# temperature_sensor.net
KiCad netlist of a schematic drawn in EAGLE
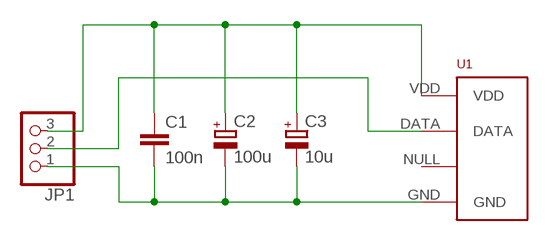
[diagram p0: schematic, sheet 1]

(export (version "E")
  (design (tool "Eeschema 10.0.6"))
  (components
    (comp (ref "C1")
      (value "100n")
      (footprint "eagle-import:C050-024X044")
      (libsource (lib "eagle-import") (part "C-EU050-024X044"))
    )
    (comp (ref "C2")
      (value "100u")
      (footprint "eagle-import:E2-5")
      (libsource (lib "eagle-import") (part "CPOL-EUE2-5"))
    )
    (comp (ref "C3")
      (value "10u")
      (footprint "eagle-import:E1,8-4")
      (libsource (lib "eagle-import") (part "CPOL-EUE1.8-4"))
    )
    (comp (ref "JP1")
      (value "PINHD-1X3")
      (footprint "eagle-import:1X03")
      (libsource (lib "eagle-import") (part "PINHD-1X3"))
    )
    (comp (ref "U1")
      (value "RHT03_DHT-22_AM2302RA")
      (footprint "eagle-import:RHT03_DHT-22_RA")
      (libsource (lib "eagle-import") (part "RHT03_DHT-22_AM2302RA"))
    )
  )
  (nets
    (net (code "1") (name "Net-(C1-Pad1)") (class "Default")
      (node (ref "C1") (pin "1") (pinfunction "1_1") (pintype "passive"))
      (node (ref "C2") (pin "+") (pinfunction "+_+") (pintype "passive"))
      (node (ref "C3") (pin "+") (pinfunction "+_+") (pintype "passive"))
      (node (ref "JP1") (pin "3") (pinfunction "3_3") (pintype "passive"))
      (node (ref "U1") (pin "VDD") (pinfunction "VDD_VDD") (pintype "power_in"))
    )
    (net (code "2") (name "Net-(C1-Pad2)") (class "Default")
      (node (ref "C1") (pin "2") (pinfunction "2_2") (pintype "passive"))
      (node (ref "C2") (pin "-") (pinfunction "-_-") (pintype "passive"))
      (node (ref "C3") (pin "-") (pinfunction "-_-") (pintype "passive"))
      (node (ref "JP1") (pin "1") (pinfunction "1_1") (pintype "passive"))
      (node (ref "U1") (pin "GND") (pinfunction "GND_GND") (pintype "power_in"))
    )
    (net (code "3") (name "Net-(JP1-Pad2)") (class "Default")
      (node (ref "JP1") (pin "2") (pinfunction "2_2") (pintype "passive"))
      (node (ref "U1") (pin "DATA") (pinfunction "DATA_DATA") (pintype "bidirectional"))
    )
    (net (code "4") (name "unconnected-(U1-PadNULL)") (class "Default")
      (node (ref "U1") (pin "NULL") (pinfunction "NULL_NULL") (pintype "no_connect"))
    )
  )
)
